# MiSTer_Vector_v1_0.net
KiCad netlist of a schematic drawn in EAGLE
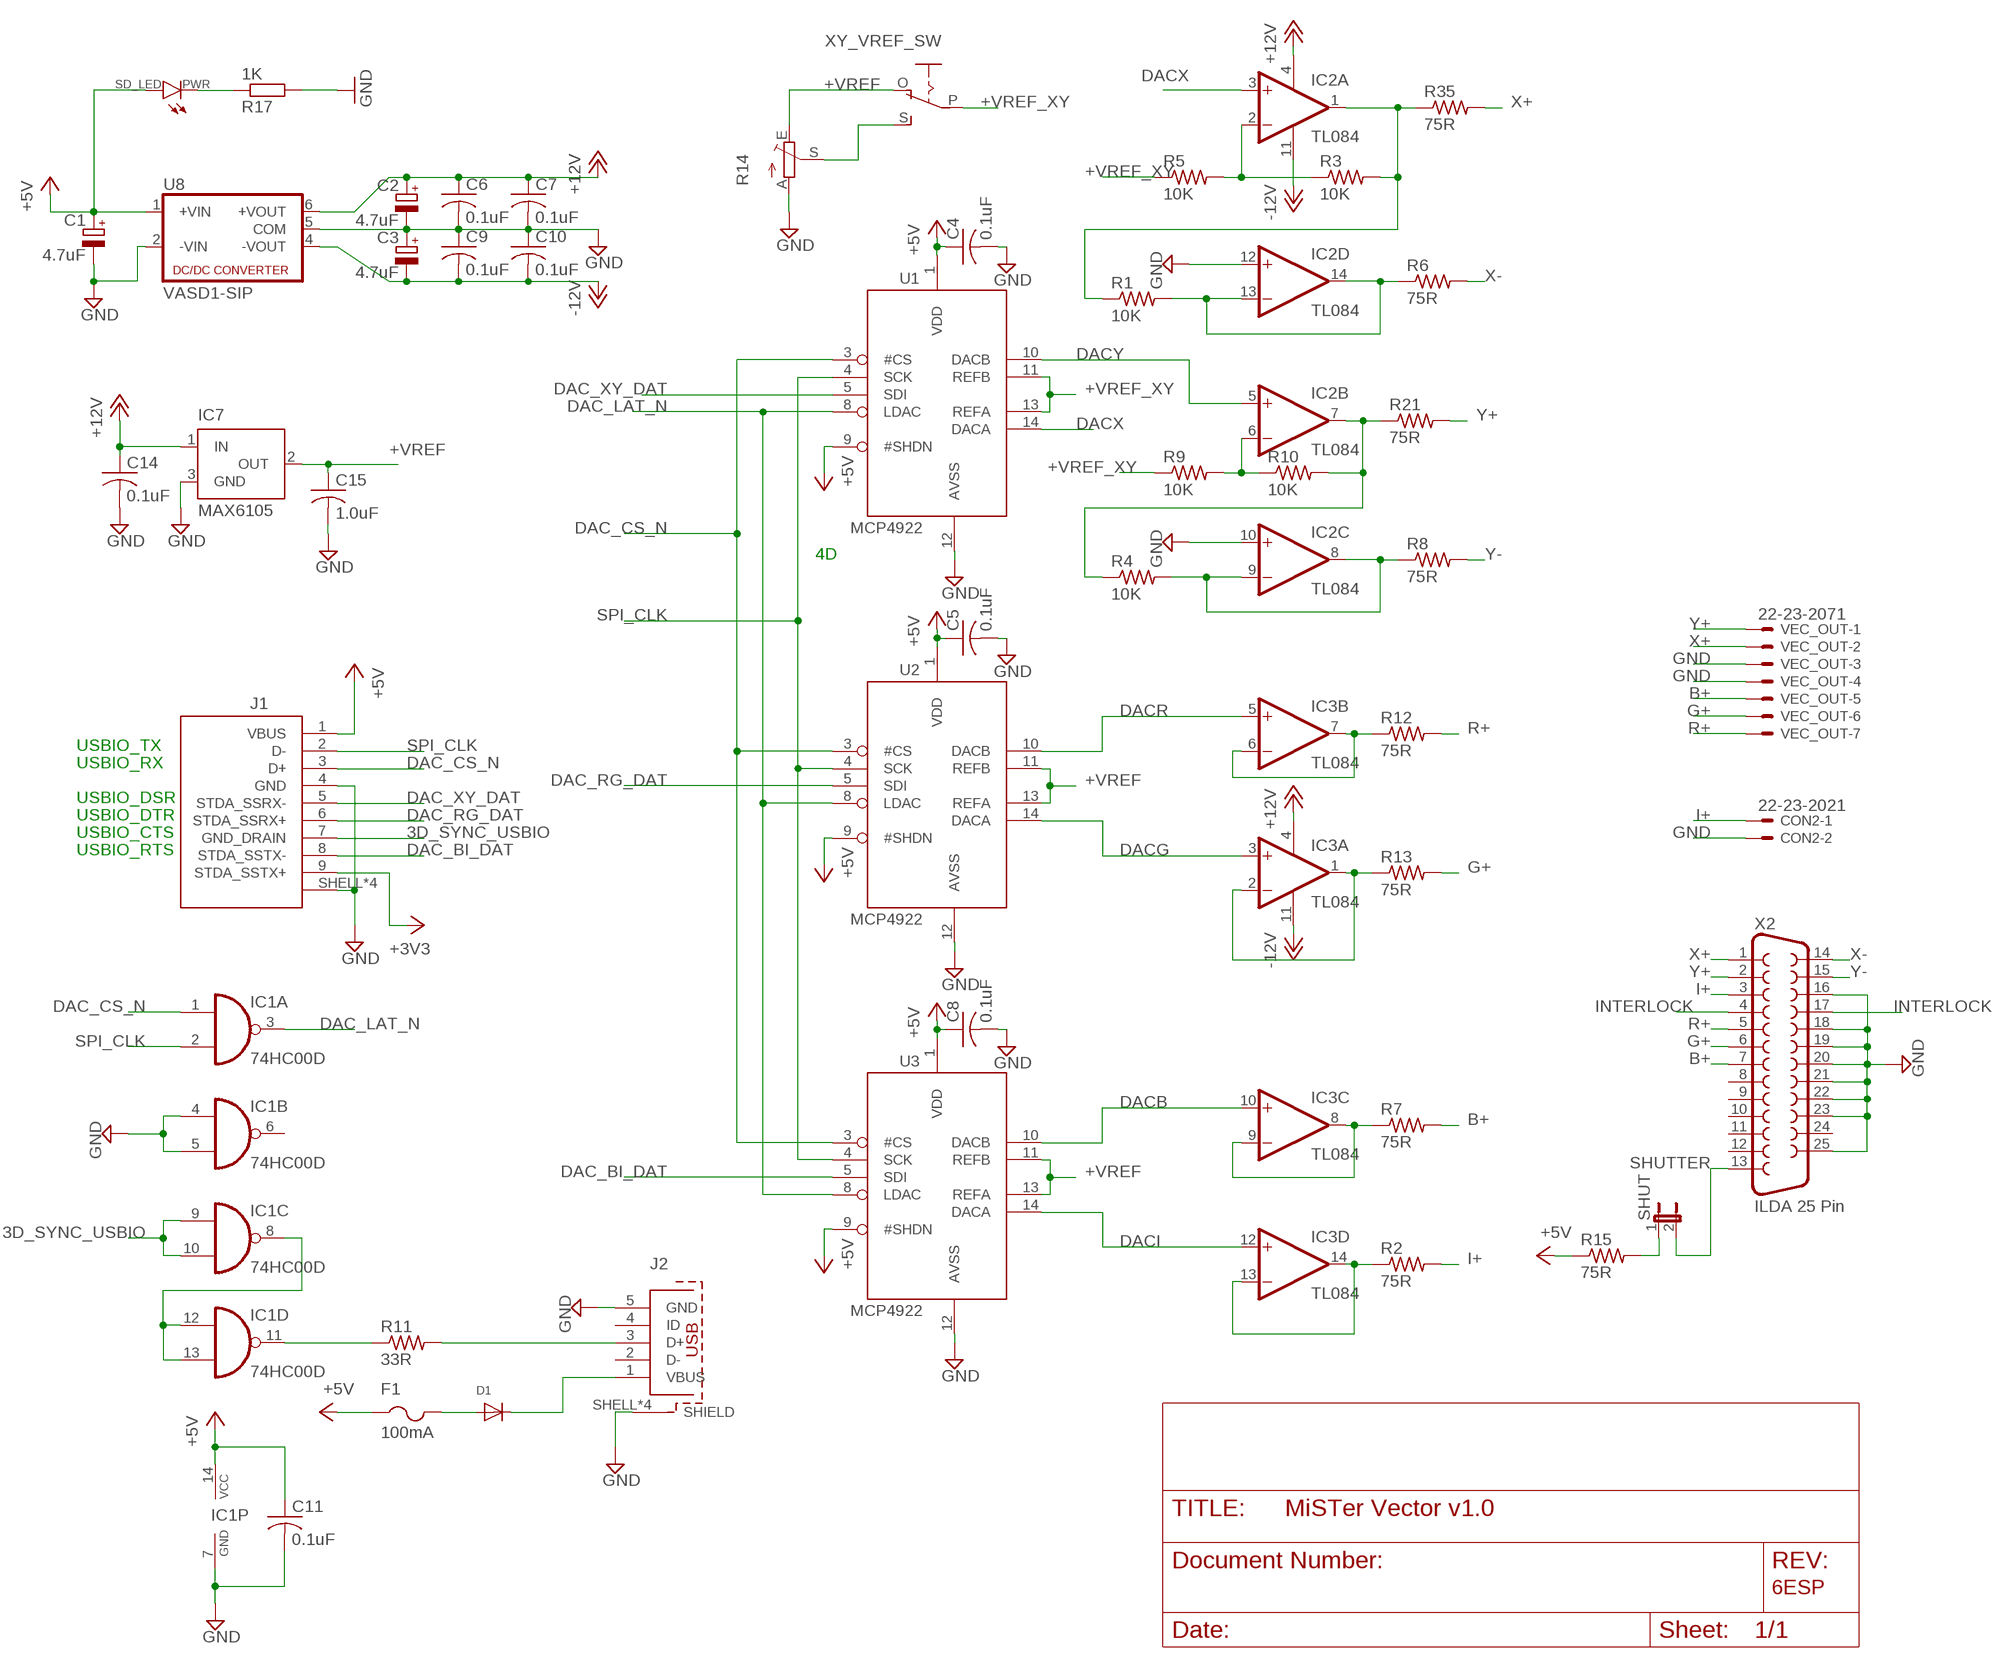
[diagram p0: schematic, sheet 1]

(export (version "E")
  (design (tool "Eeschema 10.0.6"))
  (components
    (comp (ref "C1")
      (value "4.7uF")
      (footprint "eagle-import:CT6032")
      (libsource (lib "eagle-import") (part "CPOL-EUCT6032"))
    )
    (comp (ref "C2")
      (value "4.7uF")
      (footprint "eagle-import:CT6032")
      (libsource (lib "eagle-import") (part "CPOL-EUCT6032"))
    )
    (comp (ref "C3")
      (value "4.7uF")
      (footprint "eagle-import:CT6032")
      (libsource (lib "eagle-import") (part "CPOL-EUCT6032"))
    )
    (comp (ref "C4")
      (value "0.1uF")
      (footprint "eagle-import:C0603")
      (libsource (lib "eagle-import") (part "C-USC0603"))
    )
    (comp (ref "C5")
      (value "0.1uF")
      (footprint "eagle-import:C0603")
      (libsource (lib "eagle-import") (part "C-USC0603"))
    )
    (comp (ref "C6")
      (value "0.1uF")
      (footprint "eagle-import:C0603")
      (libsource (lib "eagle-import") (part "C-USC0603"))
    )
    (comp (ref "C7")
      (value "0.1uF")
      (footprint "eagle-import:C0603")
      (libsource (lib "eagle-import") (part "C-USC0603"))
    )
    (comp (ref "C8")
      (value "0.1uF")
      (footprint "eagle-import:C0603")
      (libsource (lib "eagle-import") (part "C-USC0603"))
    )
    (comp (ref "C9")
      (value "0.1uF")
      (footprint "eagle-import:C0603")
      (libsource (lib "eagle-import") (part "C-USC0603"))
    )
    (comp (ref "C10")
      (value "0.1uF")
      (footprint "eagle-import:C0603")
      (libsource (lib "eagle-import") (part "C-USC0603"))
    )
    (comp (ref "C11")
      (value "0.1uF")
      (footprint "eagle-import:C0603")
      (libsource (lib "eagle-import") (part "C-USC0603"))
    )
    (comp (ref "C14")
      (value "0.1uF")
      (footprint "eagle-import:C0603")
      (libsource (lib "eagle-import") (part "C-USC0603"))
    )
    (comp (ref "C15")
      (value "1.0uF")
      (footprint "eagle-import:C0603")
      (libsource (lib "eagle-import") (part "C-USC0603"))
    )
    (comp (ref "CON2")
      (value "22-23-2021")
      (footprint "eagle-import:22-23-2021")
      (fields (field (name "MF") "MOLEX"))
      (libsource (lib "eagle-import") (part "22-23-2021"))
    )
    (comp (ref "D1")
      (value "DIODESOD-323F")
      (footprint "eagle-import:SOD-323F")
      (libsource (lib "eagle-import") (part "DIODESOD-323F"))
    )
    (comp (ref "F1")
      (value "100mA")
      (footprint "eagle-import:R1206")
      (libsource (lib "eagle-import") (part "PTCFUSE-1206"))
    )
    (comp (ref "IC1")
      (value "74HC00D")
      (footprint "eagle-import:SO14")
      (libsource (lib "eagle-import") (part "7400DHC"))
    )
    (comp (ref "IC2")
      (value "TL084")
      (footprint "eagle-import:SOIC-14")
      (libsource (lib "eagle-import") (part "TL084"))
    )
    (comp (ref "IC3")
      (value "TL084")
      (footprint "eagle-import:SOIC-14")
      (libsource (lib "eagle-import") (part "TL084"))
    )
    (comp (ref "IC7")
      (value "MAX6105")
      (footprint "eagle-import:SOT23")
      (fields (field (name "MF") "MAXIM") (field (name "MPN") "MAX6520EUR-T"))
      (libsource (lib "eagle-import") (part "MAX6520"))
    )
    (comp (ref "J1")
      (value "692121230100")
      (footprint "eagle-import:692121230100")
      (libsource (lib "eagle-import") (part "692121230100"))
    )
    (comp (ref "J2")
      (value "65100516121")
      (footprint "eagle-import:65100516121")
      (libsource (lib "eagle-import") (part "65100516121"))
    )
    (comp (ref "PWR")
      (value "SD_LED")
      (footprint "eagle-import:0805_POL")
      (libsource (lib "eagle-import") (part "LED0805"))
    )
    (comp (ref "R1")
      (value "10K")
      (footprint "eagle-import:R0603")
      (libsource (lib "eagle-import") (part "R-US_R0603"))
    )
    (comp (ref "R2")
      (value "75R")
      (footprint "eagle-import:R0603")
      (libsource (lib "eagle-import") (part "R-US_R0603"))
    )
    (comp (ref "R3")
      (value "10K")
      (footprint "eagle-import:R0603")
      (libsource (lib "eagle-import") (part "R-US_R0603"))
    )
    (comp (ref "R4")
      (value "10K")
      (footprint "eagle-import:R0603")
      (libsource (lib "eagle-import") (part "R-US_R0603"))
    )
    (comp (ref "R5")
      (value "10K")
      (footprint "eagle-import:R0603")
      (libsource (lib "eagle-import") (part "R-US_R0603"))
    )
    (comp (ref "R6")
      (value "75R")
      (footprint "eagle-import:R0603")
      (libsource (lib "eagle-import") (part "R-US_R0603"))
    )
    (comp (ref "R7")
      (value "75R")
      (footprint "eagle-import:R0603")
      (libsource (lib "eagle-import") (part "R-US_R0603"))
    )
    (comp (ref "R8")
      (value "75R")
      (footprint "eagle-import:R0603")
      (libsource (lib "eagle-import") (part "R-US_R0603"))
    )
    (comp (ref "R9")
      (value "10K")
      (footprint "eagle-import:R0603")
      (libsource (lib "eagle-import") (part "R-US_R0603"))
    )
    (comp (ref "R10")
      (value "10K")
      (footprint "eagle-import:R0603")
      (libsource (lib "eagle-import") (part "R-US_R0603"))
    )
    (comp (ref "R11")
      (value "33R")
      (footprint "eagle-import:R0603")
      (libsource (lib "eagle-import") (part "R-US_R0603"))
    )
    (comp (ref "R12")
      (value "75R")
      (footprint "eagle-import:R0603")
      (libsource (lib "eagle-import") (part "R-US_R0603"))
    )
    (comp (ref "R13")
      (value "75R")
      (footprint "eagle-import:R0603")
      (libsource (lib "eagle-import") (part "R-US_R0603"))
    )
    (comp (ref "R14")
      (value "TRIM_EU-B25P")
      (footprint "eagle-import:B25P")
      (libsource (lib "eagle-import") (part "TRIM_EU-B25P"))
    )
    (comp (ref "R15")
      (value "75R")
      (footprint "eagle-import:R0603")
      (libsource (lib "eagle-import") (part "R-US_R0603"))
    )
    (comp (ref "R17")
      (value "1K")
      (footprint "eagle-import:R0603")
      (libsource (lib "eagle-import") (part "R-EU_R0603"))
    )
    (comp (ref "R21")
      (value "75R")
      (footprint "eagle-import:R0603")
      (libsource (lib "eagle-import") (part "R-US_R0603"))
    )
    (comp (ref "R35")
      (value "75R")
      (footprint "eagle-import:R0603")
      (libsource (lib "eagle-import") (part "R-US_R0603"))
    )
    (comp (ref "SHUT")
      (value "JP1E")
      (footprint "eagle-import:JP1")
      (libsource (lib "eagle-import") (part "JP1E"))
    )
    (comp (ref "U1")
      (value "MCP4922")
      (footprint "eagle-import:SOIC-14")
      (libsource (lib "eagle-import") (part "MCP4922"))
    )
    (comp (ref "U2")
      (value "MCP4922")
      (footprint "eagle-import:SOIC-14")
      (libsource (lib "eagle-import") (part "MCP4922"))
    )
    (comp (ref "U3")
      (value "MCP4922")
      (footprint "eagle-import:SOIC-14")
      (libsource (lib "eagle-import") (part "MCP4922"))
    )
    (comp (ref "U8")
      (value "VASD1-SIP")
      (footprint "eagle-import:NMA")
      (fields (field (name "MF") "C & D TECHNOLOGIES, INC") (field (name "MPN") "NMA0515SC"))
      (libsource (lib "eagle-import") (part "NMA"))
    )
    (comp (ref "VEC_OUT")
      (value "22-23-2071")
      (footprint "eagle-import:22-23-2071")
      (fields (field (name "MF") "MOLEX"))
      (libsource (lib "eagle-import") (part "22-23-2071"))
    )
    (comp (ref "X2")
      (value "ILDA 25 Pin")
      (footprint "eagle-import:F25D")
      (libsource (lib "eagle-import") (part "F25D"))
    )
    (comp (ref "XY_VREF_SW")
      (value "EG1218S")
      (footprint "eagle-import:EG1218")
      (libsource (lib "eagle-import") (part "EG1218S"))
    )
  )
  (nets
    (net (code "1") (name "+3V3") (class "Default")
      (node (ref "J1") (pin "9") (pinfunction "STDA_SSTX+_9") (pintype "bidirectional"))
    )
    (net (code "2") (name "+5V") (class "Default")
      (node (ref "C1") (pin "+") (pinfunction "+_+") (pintype "passive"))
      (node (ref "C11") (pin "1") (pinfunction "1_1") (pintype "passive"))
      (node (ref "C4") (pin "1") (pinfunction "1_1") (pintype "passive"))
      (node (ref "C5") (pin "1") (pinfunction "1_1") (pintype "passive"))
      (node (ref "C8") (pin "1") (pinfunction "1_1") (pintype "passive"))
      (node (ref "F1") (pin "1") (pinfunction "1_1") (pintype "passive"))
      (node (ref "IC1") (pin "14") (pinfunction "VCC_14") (pintype "power_in"))
      (node (ref "J1") (pin "1") (pinfunction "VBUS_1") (pintype "bidirectional"))
      (node (ref "PWR") (pin "+") (pinfunction "A_+") (pintype "passive"))
      (node (ref "R15") (pin "1") (pinfunction "1_1") (pintype "passive"))
      (node (ref "U1") (pin "1") (pinfunction "VDD_1") (pintype "power_in"))
      (node (ref "U1") (pin "9") (pinfunction "#SHDN_9") (pintype "input"))
      (node (ref "U2") (pin "1") (pinfunction "VDD_1") (pintype "power_in"))
      (node (ref "U2") (pin "9") (pinfunction "#SHDN_9") (pintype "input"))
      (node (ref "U3") (pin "1") (pinfunction "VDD_1") (pintype "power_in"))
      (node (ref "U3") (pin "9") (pinfunction "#SHDN_9") (pintype "input"))
      (node (ref "U8") (pin "1") (pinfunction "+VIN_1") (pintype "passive"))
    )
    (net (code "3") (name "+12V") (class "Default")
      (node (ref "C14") (pin "1") (pinfunction "1_1") (pintype "passive"))
      (node (ref "C2") (pin "+") (pinfunction "+_+") (pintype "passive"))
      (node (ref "C6") (pin "1") (pinfunction "1_1") (pintype "passive"))
      (node (ref "C7") (pin "1") (pinfunction "1_1") (pintype "passive"))
      (node (ref "IC2") (pin "4") (pinfunction "V+_4") (pintype "power_in"))
      (node (ref "IC3") (pin "4") (pinfunction "V+_4") (pintype "power_in"))
      (node (ref "IC7") (pin "1") (pinfunction "IN_1") (pintype "input"))
      (node (ref "U8") (pin "6") (pinfunction "+VOUT_6") (pintype "passive"))
    )
    (net (code "4") (name "-12V") (class "Default")
      (node (ref "C10") (pin "2") (pinfunction "2_2") (pintype "passive"))
      (node (ref "C3") (pin "-") (pinfunction "-_-") (pintype "passive"))
      (node (ref "C9") (pin "2") (pinfunction "2_2") (pintype "passive"))
      (node (ref "IC2") (pin "11") (pinfunction "V-_11") (pintype "power_in"))
      (node (ref "IC3") (pin "11") (pinfunction "V-_11") (pintype "power_in"))
      (node (ref "U8") (pin "4") (pinfunction "-VOUT_4") (pintype "passive"))
    )
    (net (code "5") (name "/+VREF") (class "Default")
      (node (ref "C15") (pin "1") (pinfunction "1_1") (pintype "passive"))
      (node (ref "IC7") (pin "2") (pinfunction "OUT_2") (pintype "output"))
      (node (ref "R14") (pin "E") (pinfunction "E_E") (pintype "passive"))
      (node (ref "U2") (pin "11") (pinfunction "REFB_11") (pintype "input"))
      (node (ref "U2") (pin "13") (pinfunction "REFA_13") (pintype "input"))
      (node (ref "U3") (pin "11") (pinfunction "REFB_11") (pintype "input"))
      (node (ref "U3") (pin "13") (pinfunction "REFA_13") (pintype "input"))
      (node (ref "XY_VREF_SW") (pin "O") (pinfunction "O_O") (pintype "passive"))
    )
    (net (code "6") (name "/+VREF_XY") (class "Default")
      (node (ref "R5") (pin "1") (pinfunction "1_1") (pintype "passive"))
      (node (ref "R9") (pin "1") (pinfunction "1_1") (pintype "passive"))
      (node (ref "U1") (pin "11") (pinfunction "REFB_11") (pintype "input"))
      (node (ref "U1") (pin "13") (pinfunction "REFA_13") (pintype "input"))
      (node (ref "XY_VREF_SW") (pin "P") (pinfunction "P_P") (pintype "passive"))
    )
    (net (code "7") (name "/3D_SYNC_USBIO") (class "Default")
      (node (ref "IC1") (pin "10") (pinfunction "I1_10") (pintype "input"))
      (node (ref "IC1") (pin "9") (pinfunction "I0_9") (pintype "input"))
      (node (ref "J1") (pin "7") (pinfunction "GND_DRAIN_7") (pintype "bidirectional"))
    )
    (net (code "8") (name "/B+") (class "Default")
      (node (ref "R7") (pin "2") (pinfunction "2_2") (pintype "passive"))
      (node (ref "VEC_OUT") (pin "5") (pinfunction "S_5") (pintype "passive"))
      (node (ref "X2") (pin "7") (pinfunction "7_7") (pintype "passive"))
    )
    (net (code "9") (name "/DACB") (class "Default")
      (node (ref "IC3") (pin "10") (pinfunction "+IN_10") (pintype "input"))
      (node (ref "U3") (pin "10") (pinfunction "DACB_10") (pintype "output"))
    )
    (net (code "10") (name "/DACG") (class "Default")
      (node (ref "IC3") (pin "3") (pinfunction "+IN_3") (pintype "input"))
      (node (ref "U2") (pin "14") (pinfunction "DACA_14") (pintype "output"))
    )
    (net (code "11") (name "/DACI") (class "Default")
      (node (ref "IC3") (pin "12") (pinfunction "+IN_12") (pintype "input"))
      (node (ref "U3") (pin "14") (pinfunction "DACA_14") (pintype "output"))
    )
    (net (code "12") (name "/DACR") (class "Default")
      (node (ref "IC3") (pin "5") (pinfunction "+IN_5") (pintype "input"))
      (node (ref "U2") (pin "10") (pinfunction "DACB_10") (pintype "output"))
    )
    (net (code "13") (name "/DACX") (class "Default")
      (node (ref "IC2") (pin "3") (pinfunction "+IN_3") (pintype "input"))
      (node (ref "U1") (pin "14") (pinfunction "DACA_14") (pintype "output"))
    )
    (net (code "14") (name "/DACY") (class "Default")
      (node (ref "IC2") (pin "5") (pinfunction "+IN_5") (pintype "input"))
      (node (ref "U1") (pin "10") (pinfunction "DACB_10") (pintype "output"))
    )
    (net (code "15") (name "/DAC_BI_DAT") (class "Default")
      (node (ref "J1") (pin "8") (pinfunction "STDA_SSTX-_8") (pintype "bidirectional"))
      (node (ref "U3") (pin "5") (pinfunction "SDI_5") (pintype "input"))
    )
    (net (code "16") (name "/DAC_CS_N") (class "Default")
      (node (ref "IC1") (pin "1") (pinfunction "I0_1") (pintype "input"))
      (node (ref "J1") (pin "3") (pinfunction "D+_3") (pintype "bidirectional"))
      (node (ref "U1") (pin "3") (pinfunction "#CS_3") (pintype "input"))
      (node (ref "U2") (pin "3") (pinfunction "#CS_3") (pintype "input"))
      (node (ref "U3") (pin "3") (pinfunction "#CS_3") (pintype "input"))
    )
    (net (code "17") (name "/DAC_LAT_N") (class "Default")
      (node (ref "IC1") (pin "3") (pinfunction "O_3") (pintype "output"))
      (node (ref "U1") (pin "8") (pinfunction "LDAC_8") (pintype "input"))
      (node (ref "U2") (pin "8") (pinfunction "LDAC_8") (pintype "input"))
      (node (ref "U3") (pin "8") (pinfunction "LDAC_8") (pintype "input"))
    )
    (net (code "18") (name "/DAC_RG_DAT") (class "Default")
      (node (ref "J1") (pin "6") (pinfunction "STDA_SSRX+_6") (pintype "bidirectional"))
      (node (ref "U2") (pin "5") (pinfunction "SDI_5") (pintype "input"))
    )
    (net (code "19") (name "/DAC_XY_DAT") (class "Default")
      (node (ref "J1") (pin "5") (pinfunction "STDA_SSRX-_5") (pintype "bidirectional"))
      (node (ref "U1") (pin "5") (pinfunction "SDI_5") (pintype "input"))
    )
    (net (code "20") (name "/G+") (class "Default")
      (node (ref "R13") (pin "2") (pinfunction "2_2") (pintype "passive"))
      (node (ref "VEC_OUT") (pin "6") (pinfunction "S_6") (pintype "passive"))
      (node (ref "X2") (pin "6") (pinfunction "6_6") (pintype "passive"))
    )
    (net (code "21") (name "/I+") (class "Default")
      (node (ref "CON2") (pin "1") (pinfunction "S_1") (pintype "passive"))
      (node (ref "R2") (pin "2") (pinfunction "2_2") (pintype "passive"))
      (node (ref "X2") (pin "3") (pinfunction "3_3") (pintype "passive"))
    )
    (net (code "22") (name "/INTERLOCK") (class "Default")
      (node (ref "X2") (pin "17") (pinfunction "17_17") (pintype "passive"))
      (node (ref "X2") (pin "4") (pinfunction "4_4") (pintype "passive"))
    )
    (net (code "23") (name "/R+") (class "Default")
      (node (ref "R12") (pin "2") (pinfunction "2_2") (pintype "passive"))
      (node (ref "VEC_OUT") (pin "7") (pinfunction "S_7") (pintype "passive"))
      (node (ref "X2") (pin "5") (pinfunction "5_5") (pintype "passive"))
    )
    (net (code "24") (name "/SHUTTER") (class "Default")
      (node (ref "SHUT") (pin "2") (pinfunction "2_2") (pintype "passive"))
      (node (ref "X2") (pin "13") (pinfunction "13_13") (pintype "passive"))
    )
    (net (code "25") (name "/SPI_CLK") (class "Default")
      (node (ref "IC1") (pin "2") (pinfunction "I1_2") (pintype "input"))
      (node (ref "J1") (pin "2") (pinfunction "D-_2") (pintype "bidirectional"))
      (node (ref "U1") (pin "4") (pinfunction "SCK_4") (pintype "input"))
      (node (ref "U2") (pin "4") (pinfunction "SCK_4") (pintype "input"))
      (node (ref "U3") (pin "4") (pinfunction "SCK_4") (pintype "input"))
    )
    (net (code "26") (name "/X+") (class "Default")
      (node (ref "R35") (pin "2") (pinfunction "2_2") (pintype "passive"))
      (node (ref "VEC_OUT") (pin "2") (pinfunction "S_2") (pintype "passive"))
      (node (ref "X2") (pin "1") (pinfunction "1_1") (pintype "passive"))
    )
    (net (code "27") (name "/X-") (class "Default")
      (node (ref "R6") (pin "2") (pinfunction "2_2") (pintype "passive"))
      (node (ref "X2") (pin "14") (pinfunction "14_14") (pintype "passive"))
    )
    (net (code "28") (name "/Y+") (class "Default")
      (node (ref "R21") (pin "2") (pinfunction "2_2") (pintype "passive"))
      (node (ref "VEC_OUT") (pin "1") (pinfunction "S_1") (pintype "passive"))
      (node (ref "X2") (pin "2") (pinfunction "2_2") (pintype "passive"))
    )
    (net (code "29") (name "/Y-") (class "Default")
      (node (ref "R8") (pin "2") (pinfunction "2_2") (pintype "passive"))
      (node (ref "X2") (pin "15") (pinfunction "15_15") (pintype "passive"))
    )
    (net (code "30") (name "GND") (class "Default")
      (node (ref "C1") (pin "-") (pinfunction "-_-") (pintype "passive"))
      (node (ref "C10") (pin "1") (pinfunction "1_1") (pintype "passive"))
      (node (ref "C11") (pin "2") (pinfunction "2_2") (pintype "passive"))
      (node (ref "C14") (pin "2") (pinfunction "2_2") (pintype "passive"))
      (node (ref "C15") (pin "2") (pinfunction "2_2") (pintype "passive"))
      (node (ref "C2") (pin "-") (pinfunction "-_-") (pintype "passive"))
      (node (ref "C3") (pin "+") (pinfunction "+_+") (pintype "passive"))
      (node (ref "C4") (pin "2") (pinfunction "2_2") (pintype "passive"))
      (node (ref "C5") (pin "2") (pinfunction "2_2") (pintype "passive"))
      (node (ref "C6") (pin "2") (pinfunction "2_2") (pintype "passive"))
      (node (ref "C7") (pin "2") (pinfunction "2_2") (pintype "passive"))
      (node (ref "C8") (pin "2") (pinfunction "2_2") (pintype "passive"))
      (node (ref "C9") (pin "1") (pinfunction "1_1") (pintype "passive"))
      (node (ref "CON2") (pin "2") (pinfunction "S_2") (pintype "passive"))
      (node (ref "IC1") (pin "4") (pinfunction "I0_4") (pintype "input"))
      (node (ref "IC1") (pin "5") (pinfunction "I1_5") (pintype "input"))
      (node (ref "IC1") (pin "7") (pinfunction "GND_7") (pintype "power_in"))
      (node (ref "IC2") (pin "10") (pinfunction "+IN_10") (pintype "input"))
      (node (ref "IC2") (pin "12") (pinfunction "+IN_12") (pintype "input"))
      (node (ref "IC7") (pin "3") (pinfunction "GND_3") (pintype "power_in"))
      (node (ref "J1") (pin "4") (pinfunction "GND_4") (pintype "bidirectional"))
      (node (ref "J1") (pin "SHELL") (pinfunction "SHIELD_SHELL") (pintype "bidirectional"))
      (node (ref "J1") (pin "SHELL1") (pinfunction "SHIELD_SHELL1") (pintype "bidirectional"))
      (node (ref "J1") (pin "SHELL2") (pinfunction "SHIELD_SHELL2") (pintype "bidirectional"))
      (node (ref "J1") (pin "SHELL3") (pinfunction "SHIELD_SHELL3") (pintype "bidirectional"))
      (node (ref "J2") (pin "5") (pinfunction "GND_5") (pintype "passive"))
      (node (ref "J2") (pin "SHELL") (pinfunction "SHIELD_SHELL") (pintype "passive"))
      (node (ref "J2") (pin "SHELL1") (pinfunction "SHIELD_SHELL1") (pintype "passive"))
      (node (ref "J2") (pin "SHELL2") (pinfunction "SHIELD_SHELL2") (pintype "passive"))
      (node (ref "J2") (pin "SHELL3") (pinfunction "SHIELD_SHELL3") (pintype "passive"))
      (node (ref "R14") (pin "A") (pinfunction "A_A") (pintype "passive"))
      (node (ref "R17") (pin "2") (pinfunction "2_2") (pintype "passive"))
      (node (ref "U1") (pin "12") (pinfunction "AVSS_12") (pintype "power_in"))
      (node (ref "U2") (pin "12") (pinfunction "AVSS_12") (pintype "power_in"))
      (node (ref "U3") (pin "12") (pinfunction "AVSS_12") (pintype "power_in"))
      (node (ref "U8") (pin "2") (pinfunction "-VIN_2") (pintype "passive"))
      (node (ref "U8") (pin "5") (pinfunction "COM_5") (pintype "passive"))
      (node (ref "VEC_OUT") (pin "3") (pinfunction "S_3") (pintype "passive"))
      (node (ref "VEC_OUT") (pin "4") (pinfunction "S_4") (pintype "passive"))
      (node (ref "X2") (pin "16") (pinfunction "16_16") (pintype "passive"))
      (node (ref "X2") (pin "18") (pinfunction "18_18") (pintype "passive"))
      (node (ref "X2") (pin "19") (pinfunction "19_19") (pintype "passive"))
      (node (ref "X2") (pin "20") (pinfunction "20_20") (pintype "passive"))
      (node (ref "X2") (pin "21") (pinfunction "21_21") (pintype "passive"))
      (node (ref "X2") (pin "22") (pinfunction "22_22") (pintype "passive"))
      (node (ref "X2") (pin "23") (pinfunction "23_23") (pintype "passive"))
      (node (ref "X2") (pin "25") (pinfunction "25_25") (pintype "passive"))
    )
    (net (code "31") (name "Net-(D1-PadA)") (class "Default")
      (node (ref "D1") (pin "A") (pinfunction "A_A") (pintype "passive"))
      (node (ref "F1") (pin "2") (pinfunction "2_2") (pintype "passive"))
    )
    (net (code "32") (name "Net-(IC1C-O)") (class "Default")
      (node (ref "IC1") (pin "12") (pinfunction "I0_12") (pintype "input"))
      (node (ref "IC1") (pin "13") (pinfunction "I1_13") (pintype "input"))
      (node (ref "IC1") (pin "8") (pinfunction "O_8") (pintype "output"))
    )
    (net (code "33") (name "Net-(IC1D-O)") (class "Default")
      (node (ref "IC1") (pin "11") (pinfunction "O_11") (pintype "output"))
      (node (ref "R11") (pin "1") (pinfunction "1_1") (pintype "passive"))
    )
    (net (code "34") (name "Net-(IC2A--IN)") (class "Default")
      (node (ref "IC2") (pin "2") (pinfunction "-IN_2") (pintype "input"))
      (node (ref "R3") (pin "1") (pinfunction "1_1") (pintype "passive"))
      (node (ref "R5") (pin "2") (pinfunction "2_2") (pintype "passive"))
    )
    (net (code "35") (name "Net-(IC2A-OUT)") (class "Default")
      (node (ref "IC2") (pin "1") (pinfunction "OUT_1") (pintype "output"))
      (node (ref "R1") (pin "1") (pinfunction "1_1") (pintype "passive"))
      (node (ref "R3") (pin "2") (pinfunction "2_2") (pintype "passive"))
      (node (ref "R35") (pin "1") (pinfunction "1_1") (pintype "passive"))
    )
    (net (code "36") (name "Net-(IC2B--IN)") (class "Default")
      (node (ref "IC2") (pin "6") (pinfunction "-IN_6") (pintype "input"))
      (node (ref "R10") (pin "1") (pinfunction "1_1") (pintype "passive"))
      (node (ref "R9") (pin "2") (pinfunction "2_2") (pintype "passive"))
    )
    (net (code "37") (name "Net-(IC2B-OUT)") (class "Default")
      (node (ref "IC2") (pin "7") (pinfunction "OUT_7") (pintype "output"))
      (node (ref "R10") (pin "2") (pinfunction "2_2") (pintype "passive"))
      (node (ref "R21") (pin "1") (pinfunction "1_1") (pintype "passive"))
      (node (ref "R4") (pin "1") (pinfunction "1_1") (pintype "passive"))
    )
    (net (code "38") (name "Net-(IC2C--IN)") (class "Default")
      (node (ref "IC2") (pin "8") (pinfunction "OUT_8") (pintype "output"))
      (node (ref "IC2") (pin "9") (pinfunction "-IN_9") (pintype "input"))
      (node (ref "R4") (pin "2") (pinfunction "2_2") (pintype "passive"))
      (node (ref "R8") (pin "1") (pinfunction "1_1") (pintype "passive"))
    )
    (net (code "39") (name "Net-(IC2D--IN)") (class "Default")
      (node (ref "IC2") (pin "13") (pinfunction "-IN_13") (pintype "input"))
      (node (ref "IC2") (pin "14") (pinfunction "OUT_14") (pintype "output"))
      (node (ref "R1") (pin "2") (pinfunction "2_2") (pintype "passive"))
      (node (ref "R6") (pin "1") (pinfunction "1_1") (pintype "passive"))
    )
    (net (code "40") (name "Net-(IC3A--IN)") (class "Default")
      (node (ref "IC3") (pin "1") (pinfunction "OUT_1") (pintype "output"))
      (node (ref "IC3") (pin "2") (pinfunction "-IN_2") (pintype "input"))
      (node (ref "R13") (pin "1") (pinfunction "1_1") (pintype "passive"))
    )
    (net (code "41") (name "Net-(IC3B--IN)") (class "Default")
      (node (ref "IC3") (pin "6") (pinfunction "-IN_6") (pintype "input"))
      (node (ref "IC3") (pin "7") (pinfunction "OUT_7") (pintype "output"))
      (node (ref "R12") (pin "1") (pinfunction "1_1") (pintype "passive"))
    )
    (net (code "42") (name "Net-(IC3C--IN)") (class "Default")
      (node (ref "IC3") (pin "8") (pinfunction "OUT_8") (pintype "output"))
      (node (ref "IC3") (pin "9") (pinfunction "-IN_9") (pintype "input"))
      (node (ref "R7") (pin "1") (pinfunction "1_1") (pintype "passive"))
    )
    (net (code "43") (name "Net-(IC3D--IN)") (class "Default")
      (node (ref "IC3") (pin "13") (pinfunction "-IN_13") (pintype "input"))
      (node (ref "IC3") (pin "14") (pinfunction "OUT_14") (pintype "output"))
      (node (ref "R2") (pin "1") (pinfunction "1_1") (pintype "passive"))
    )
    (net (code "44") (name "Net-(J2-D+)") (class "Default")
      (node (ref "J2") (pin "3") (pinfunction "D+_3") (pintype "passive"))
      (node (ref "R11") (pin "2") (pinfunction "2_2") (pintype "passive"))
    )
    (net (code "45") (name "Net-(J2-VBUS)") (class "Default")
      (node (ref "D1") (pin "C") (pinfunction "C_C") (pintype "passive"))
      (node (ref "J2") (pin "1") (pinfunction "VBUS_1") (pintype "passive"))
    )
    (net (code "46") (name "Net-(PWR-C)") (class "Default")
      (node (ref "PWR") (pin "-") (pinfunction "C_-") (pintype "passive"))
      (node (ref "R17") (pin "1") (pinfunction "1_1") (pintype "passive"))
    )
    (net (code "47") (name "Net-(R14-PadS)") (class "Default")
      (node (ref "R14") (pin "S") (pinfunction "S_S") (pintype "passive"))
      (node (ref "XY_VREF_SW") (pin "S") (pinfunction "S_S") (pintype "passive"))
    )
    (net (code "48") (name "Net-(R15-Pad2)") (class "Default")
      (node (ref "R15") (pin "2") (pinfunction "2_2") (pintype "passive"))
      (node (ref "SHUT") (pin "1") (pinfunction "1_1") (pintype "passive"))
    )
    (net (code "49") (name "unconnected-(IC1B-O-Pad6)") (class "Default")
      (node (ref "IC1") (pin "6") (pinfunction "O_6") (pintype "output"))
    )
    (net (code "50") (name "unconnected-(J2-D--Pad2)") (class "Default")
      (node (ref "J2") (pin "2") (pinfunction "D-_2") (pintype "passive"))
    )
    (net (code "51") (name "unconnected-(J2-ID-Pad4)") (class "Default")
      (node (ref "J2") (pin "4") (pinfunction "ID_4") (pintype "passive"))
    )
    (net (code "52") (name "unconnected-(X2-Pad8)") (class "Default")
      (node (ref "X2") (pin "8") (pinfunction "8_8") (pintype "passive"))
    )
    (net (code "53") (name "unconnected-(X2-Pad9)") (class "Default")
      (node (ref "X2") (pin "9") (pinfunction "9_9") (pintype "passive"))
    )
    (net (code "54") (name "unconnected-(X2-Pad10)") (class "Default")
      (node (ref "X2") (pin "10") (pinfunction "10_10") (pintype "passive"))
    )
    (net (code "55") (name "unconnected-(X2-Pad11)") (class "Default")
      (node (ref "X2") (pin "11") (pinfunction "11_11") (pintype "passive"))
    )
    (net (code "56") (name "unconnected-(X2-Pad12)") (class "Default")
      (node (ref "X2") (pin "12") (pinfunction "12_12") (pintype "passive"))
    )
    (net (code "57") (name "unconnected-(X2-Pad24)") (class "Default")
      (node (ref "X2") (pin "24") (pinfunction "24_24") (pintype "passive"))
    )
  )
)
